# sm.net
KiCad netlist of a schematic drawn in Altium Designer
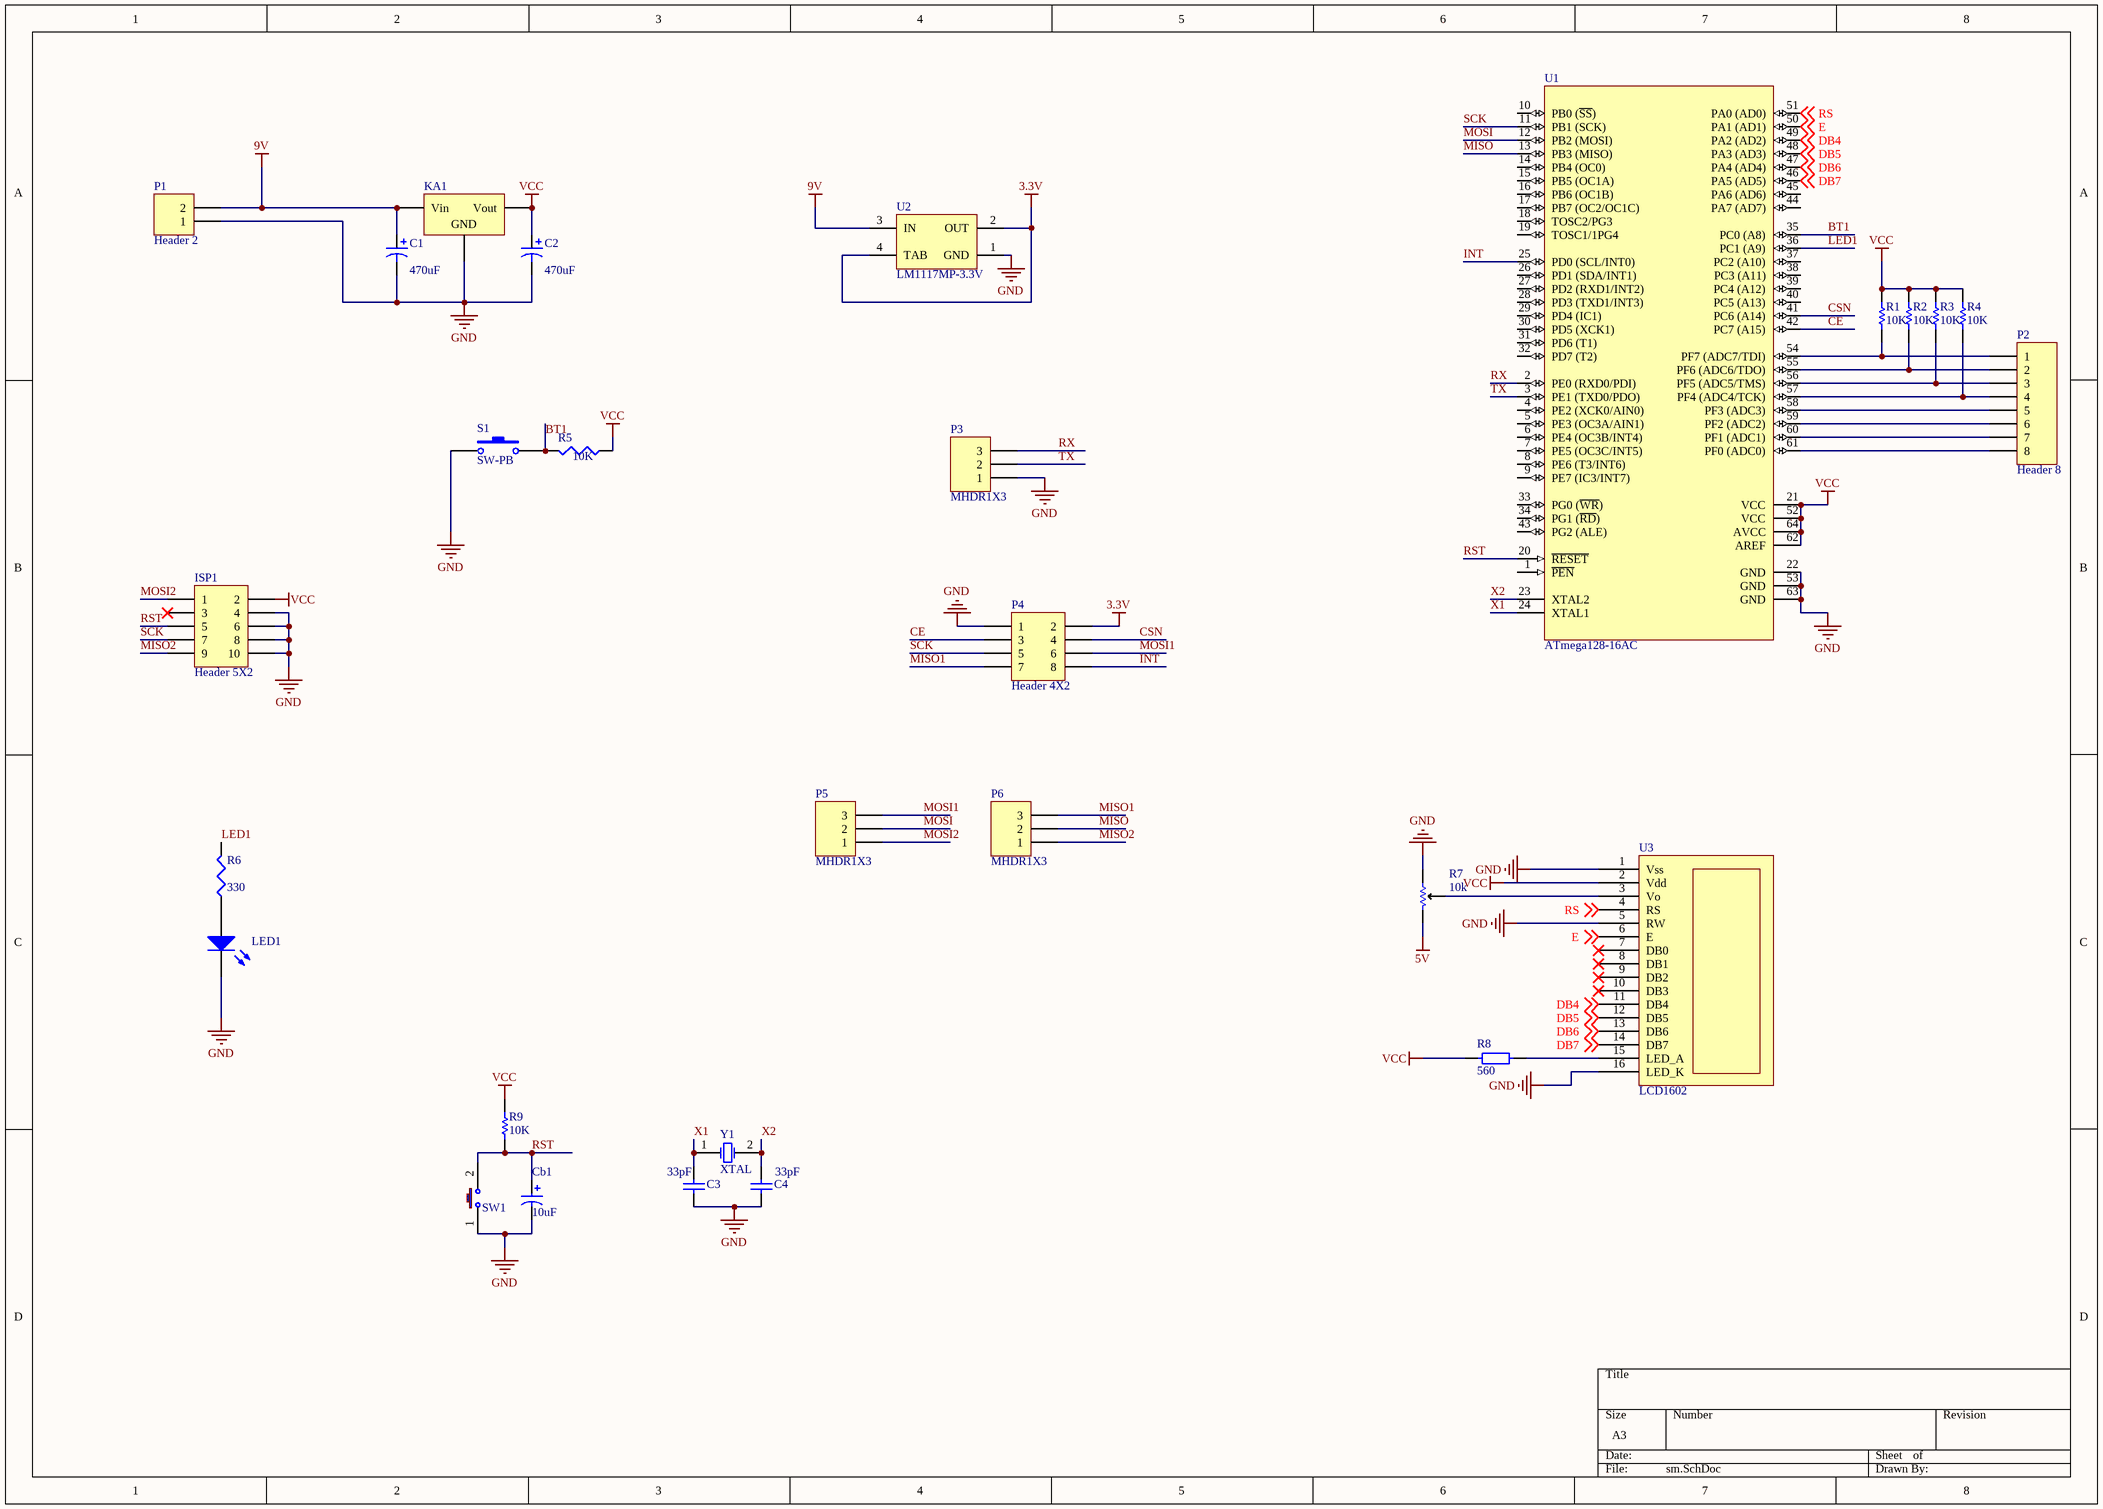
[diagram p0: sm.SchDoc]

(export (version "E")
  (design (tool "Eeschema 10.0.6"))
  (components
    (comp (ref "C1")
      (value "470uF")
      (footprint "CAPPR5-5x5")
      (description "Polarized Capacitor (Radial)")
      (fields (field (name "Comment") "Cap Pol1") (field (name "PUBLISHER") "Altium Limited"))
      (libsource (lib "Miscellaneous Devices") (part "Cap Pol1"))
    )
    (comp (ref "C2")
      (value "470uF")
      (footprint "CAPPR5-5x5")
      (description "Polarized Capacitor (Radial)")
      (fields (field (name "Comment") "Cap Pol1") (field (name "PUBLISHER") "Altium Limited"))
      (libsource (lib "Miscellaneous Devices") (part "Cap Pol1"))
    )
    (comp (ref "C3")
      (value "33pF")
      (footprint "SM/C_0805")
      (description "Capacitor")
      (fields (field (name "Comment") "Cap") (field (name "PUBLISHER") "Altium Limited"))
      (libsource (lib "Miscellaneous Devices") (part "Cap"))
    )
    (comp (ref "C4")
      (value "33pF")
      (footprint "SM/C_0805")
      (description "Capacitor")
      (fields (field (name "Comment") "Cap") (field (name "PUBLISHER") "Altium Limited"))
      (libsource (lib "Miscellaneous Devices") (part "Cap"))
    )
    (comp (ref "Cb1") (value "10uF") (footprint "SM/C_0805") (libsource (lib "DUYPRO2") (part "CAP POL 250")))
    (comp (ref "ISP1")
      (value "Header 5X2")
      (footprint "HDR2X5")
      (description "Header, 5-Pin, Dual row")
      (fields (field (name "PUBLISHER") "Altium Limited"))
      (libsource (lib "Miscellaneous Connectors") (part "Header 5X2"))
    )
    (comp (ref "KA1")
      (value "Volt Reg")
      (footprint "TO-220")
      (description "Voltage Regulator")
      (fields (field (name "PUBLISHER") "Altium Limited"))
      (libsource (lib "Miscellaneous Devices") (part "Volt Reg"))
    )
    (comp (ref "LED1")
      (value "LED3")
      (footprint "DSO-C2/D5.6")
      (description "Typical BLUE SiC LED")
      (fields (field (name "PUBLISHER") "Altium Limited"))
      (libsource (lib "Miscellaneous Devices") (part "LED3"))
    )
    (comp (ref "P1")
      (value "Header 2")
      (footprint "HDR1X2")
      (description "Header, 2-Pin")
      (fields (field (name "PUBLISHER") "Altium Limited"))
      (libsource (lib "Miscellaneous Connectors") (part "Header 2"))
    )
    (comp (ref "P2")
      (value "Header 8")
      (footprint "HDR1X8")
      (description "Header, 8-Pin")
      (fields (field (name "PUBLISHER") "Altium Limited"))
      (libsource (lib "Miscellaneous Connectors") (part "Header 8"))
    )
    (comp (ref "P3")
      (value "MHDR1X3")
      (footprint "MHDR1X3")
      (description "Header, 3-Pin")
      (fields (field (name "PUBLISHER") "Altium Limited"))
      (libsource (lib "Miscellaneous Connectors") (part "MHDR1X3"))
    )
    (comp (ref "P4")
      (value "Header 4X2")
      (footprint "HDR2X4")
      (description "Header, 4-Pin, Dual row")
      (fields (field (name "PUBLISHER") "Altium Limited"))
      (libsource (lib "Miscellaneous Connectors") (part "Header 4X2"))
    )
    (comp (ref "P5")
      (value "MHDR1X3")
      (footprint "MHDR1X3")
      (description "Header, 3-Pin")
      (fields (field (name "PUBLISHER") "Altium Limited"))
      (libsource (lib "Miscellaneous Connectors") (part "MHDR1X3"))
    )
    (comp (ref "P6")
      (value "MHDR1X3")
      (footprint "MHDR1X3")
      (description "Header, 3-Pin")
      (fields (field (name "PUBLISHER") "Altium Limited"))
      (libsource (lib "Miscellaneous Connectors") (part "MHDR1X3"))
    )
    (comp (ref "R1") (value "10K") (footprint "SM/C_0805") (libsource (lib "DUYPRO2") (part "R 300")))
    (comp (ref "R2") (value "10K") (footprint "SM/C_0805") (libsource (lib "DUYPRO2") (part "R 300")))
    (comp (ref "R3") (value "10K") (footprint "SM/C_0805") (libsource (lib "DUYPRO2") (part "R 300")))
    (comp (ref "R4") (value "10K") (footprint "SM/C_0805") (libsource (lib "DUYPRO2") (part "R 300")))
    (comp (ref "R5")
      (value "10K")
      (footprint "RESC1608L")
      (description "Resistor")
      (fields (field (name "Comment") "Res3") (field (name "PUBLISHER") "Altium Limited"))
      (libsource (lib "Miscellaneous Devices") (part "Res3"))
    )
    (comp (ref "R6")
      (value "330")
      (footprint "RESC1608L")
      (description "Resistor")
      (fields (field (name "Comment") "Res3") (field (name "PUBLISHER") "Altium Limited"))
      (libsource (lib "Miscellaneous Devices") (part "Res3"))
    )
    (comp (ref "R7") (value "10k") (footprint "BienTro") (libsource (lib "FUFO") (part "BienTro")))
    (comp (ref "R8") (value "560") (footprint "SM/C_0805") (libsource (lib "FUFO") (part "Resistor")))
    (comp (ref "R9") (value "10K") (footprint "SM/C_0805") (libsource (lib "DUYPRO2") (part "R 300")))
    (comp (ref "S1")
      (value "SW-PB")
      (footprint "SPST-2")
      (description "Switch")
      (fields (field (name "PUBLISHER") "Altium Limited"))
      (libsource (lib "Miscellaneous Devices") (part "SW-PB"))
    )
    (comp (ref "SW1")
      (value "BUTTON 2 PIN")
      (footprint "KEYSMALL2")
      (libsource (lib "DUYPRO2") (part "BUTTON 2 PIN"))
    )
    (comp (ref "U1")
      (value "ATmega128-16AC")
      (footprint "64A_N")
      (description "8-Bit AVR Microcontroller with 128K Bytes of In-System Programmable Flash Memory")
      (fields (field (name "PUBLISHER") "Altium Limited"))
      (libsource (lib "Atmel Microcontroller 8-Bit AVR") (part "ATmega128-16AC"))
    )
    (comp (ref "U2")
      (value "LM1117MP-3.3V")
      (footprint "SM/SOT223_1234")
      (description "800mA Low-Dropout Linear Regulator")
      (fields
        (field (name "PARTNUMBER") "LM1117MP-3.3")
        (field (name "MANUFACTURER") "National Semiconductor")
        (field (name "PUBLISHER") "Altium Limited")
      )
      (libsource (lib "NSC LDO") (part "LM1117MP-3.3"))
    )
    (comp (ref "U3") (value "LCD1602") (footprint "LCD1602") (libsource (lib "FUFO") (part "LCD1602")))
    (comp (ref "Y1")
      (value "XTAL")
      (footprint "CAPR5.08-7.8x3.2")
      (description "Crystal Oscillator")
      (fields (field (name "PUBLISHER") "Altium Limited"))
      (libsource (lib "Miscellaneous Devices") (part "XTAL"))
    )
  )
  (nets
    (net (code "1") (name "/BT1") (class "Default")
      (node (ref "R5") (pin "2") (pinfunction "2_2") (pintype "passive"))
      (node (ref "S1") (pin "2") (pinfunction "2_2") (pintype "passive"))
      (node (ref "U1") (pin "35") (pinfunction "PC0_(A8)_35") (pintype "bidirectional"))
    )
    (net (code "2") (name "/CE") (class "Default")
      (node (ref "P4") (pin "3") (pinfunction "3_3") (pintype "passive"))
      (node (ref "U1") (pin "42") (pinfunction "PC7_(A15)_42") (pintype "bidirectional"))
    )
    (net (code "3") (name "/CSN") (class "Default")
      (node (ref "P4") (pin "4") (pinfunction "4_4") (pintype "passive"))
      (node (ref "U1") (pin "41") (pinfunction "PC6_(A14)_41") (pintype "bidirectional"))
    )
    (net (code "4") (name "/INT") (class "Default")
      (node (ref "P4") (pin "8") (pinfunction "8_8") (pintype "passive"))
      (node (ref "U1") (pin "25") (pinfunction "PD0_(SCL/INT0)_25") (pintype "bidirectional"))
    )
    (net (code "5") (name "/LED1") (class "Default")
      (node (ref "R6") (pin "2") (pinfunction "2_2") (pintype "passive"))
      (node (ref "U1") (pin "36") (pinfunction "PC1_(A9)_36") (pintype "bidirectional"))
    )
    (net (code "6") (name "/MISO") (class "Default")
      (node (ref "P6") (pin "2") (pinfunction "2_2") (pintype "passive"))
      (node (ref "U1") (pin "13") (pinfunction "PB3_(MISO)_13") (pintype "bidirectional"))
    )
    (net (code "7") (name "/MISO1") (class "Default")
      (node (ref "P4") (pin "7") (pinfunction "7_7") (pintype "passive"))
      (node (ref "P6") (pin "3") (pinfunction "3_3") (pintype "passive"))
    )
    (net (code "8") (name "/MISO2") (class "Default")
      (node (ref "ISP1") (pin "9") (pinfunction "9_9") (pintype "passive"))
      (node (ref "P6") (pin "1") (pinfunction "1_1") (pintype "passive"))
    )
    (net (code "9") (name "/MOSI") (class "Default")
      (node (ref "P5") (pin "2") (pinfunction "2_2") (pintype "passive"))
      (node (ref "U1") (pin "12") (pinfunction "PB2_(MOSI)_12") (pintype "bidirectional"))
    )
    (net (code "10") (name "/MOSI1") (class "Default")
      (node (ref "P4") (pin "6") (pinfunction "6_6") (pintype "passive"))
      (node (ref "P5") (pin "3") (pinfunction "3_3") (pintype "passive"))
    )
    (net (code "11") (name "/MOSI2") (class "Default")
      (node (ref "ISP1") (pin "1") (pinfunction "1_1") (pintype "passive"))
      (node (ref "P5") (pin "1") (pinfunction "1_1") (pintype "passive"))
    )
    (net (code "12") (name "/RST") (class "Default")
      (node (ref "Cb1") (pin "1") (pinfunction "1_1") (pintype "passive"))
      (node (ref "ISP1") (pin "5") (pinfunction "5_5") (pintype "passive"))
      (node (ref "R9") (pin "1") (pinfunction "1_1") (pintype "passive"))
      (node (ref "SW1") (pin "2") (pinfunction "2_2") (pintype "passive"))
      (node (ref "U1") (pin "20") (pinfunction "~{RESET}_20") (pintype "input"))
    )
    (net (code "13") (name "/RX") (class "Default")
      (node (ref "P3") (pin "3") (pinfunction "3_3") (pintype "passive"))
      (node (ref "U1") (pin "2") (pinfunction "PE0_(RXD0/PDI)_2") (pintype "bidirectional"))
    )
    (net (code "14") (name "/SCK") (class "Default")
      (node (ref "ISP1") (pin "7") (pinfunction "7_7") (pintype "passive"))
      (node (ref "P4") (pin "5") (pinfunction "5_5") (pintype "passive"))
      (node (ref "U1") (pin "11") (pinfunction "PB1_(SCK)_11") (pintype "bidirectional"))
    )
    (net (code "15") (name "/TX") (class "Default")
      (node (ref "P3") (pin "2") (pinfunction "2_2") (pintype "passive"))
      (node (ref "U1") (pin "3") (pinfunction "PE1_(TXD0/PDO)_3") (pintype "bidirectional"))
    )
    (net (code "16") (name "/X1") (class "Default")
      (node (ref "C3") (pin "2") (pinfunction "2_2") (pintype "passive"))
      (node (ref "U1") (pin "24") (pinfunction "XTAL1_24") (pintype "passive"))
      (node (ref "Y1") (pin "1") (pinfunction "OSC1_1") (pintype "passive"))
    )
    (net (code "17") (name "/X2") (class "Default")
      (node (ref "C4") (pin "2") (pinfunction "2_2") (pintype "passive"))
      (node (ref "U1") (pin "23") (pinfunction "XTAL2_23") (pintype "passive"))
      (node (ref "Y1") (pin "2") (pinfunction "OSC2_2") (pintype "passive"))
    )
    (net (code "18") (name "3.3V") (class "Default")
      (node (ref "P4") (pin "2") (pinfunction "2_2") (pintype "passive"))
      (node (ref "U2") (pin "2") (pinfunction "OUT_2") (pintype "power_in"))
      (node (ref "U2") (pin "4") (pinfunction "TAB_4") (pintype "power_in"))
    )
    (net (code "19") (name "5V") (class "Default")
      (node (ref "R7") (pin "2") (pinfunction "2_2") (pintype "passive"))
    )
    (net (code "20") (name "9V") (class "Default")
      (node (ref "C1") (pin "1") (pinfunction "1_1") (pintype "passive"))
      (node (ref "KA1") (pin "1") (pinfunction "Vin_1") (pintype "passive"))
      (node (ref "P1") (pin "2") (pinfunction "2_2") (pintype "passive"))
      (node (ref "U2") (pin "3") (pinfunction "IN_3") (pintype "power_in"))
    )
    (net (code "21") (name "DB4") (class "Default")
      (node (ref "U1") (pin "49") (pinfunction "PA2_(AD2)_49") (pintype "bidirectional"))
      (node (ref "U3") (pin "11") (pinfunction "DB4_11") (pintype "passive"))
    )
    (net (code "22") (name "DB5") (class "Default")
      (node (ref "U1") (pin "48") (pinfunction "PA3_(AD3)_48") (pintype "bidirectional"))
      (node (ref "U3") (pin "12") (pinfunction "DB5_12") (pintype "passive"))
    )
    (net (code "23") (name "DB6") (class "Default")
      (node (ref "U1") (pin "47") (pinfunction "PA4_(AD4)_47") (pintype "bidirectional"))
      (node (ref "U3") (pin "13") (pinfunction "DB6_13") (pintype "passive"))
    )
    (net (code "24") (name "DB7") (class "Default")
      (node (ref "U1") (pin "46") (pinfunction "PA5_(AD5)_46") (pintype "bidirectional"))
      (node (ref "U3") (pin "14") (pinfunction "DB7_14") (pintype "passive"))
    )
    (net (code "25") (name "E") (class "Default")
      (node (ref "U1") (pin "50") (pinfunction "PA1_(AD1)_50") (pintype "bidirectional"))
      (node (ref "U3") (pin "6") (pinfunction "E_6") (pintype "passive"))
    )
    (net (code "26") (name "GND") (class "Default")
      (node (ref "C1") (pin "2") (pinfunction "2_2") (pintype "passive"))
      (node (ref "C2") (pin "2") (pinfunction "2_2") (pintype "passive"))
      (node (ref "C3") (pin "1") (pinfunction "1_1") (pintype "passive"))
      (node (ref "C4") (pin "1") (pinfunction "1_1") (pintype "passive"))
      (node (ref "Cb1") (pin "2") (pinfunction "2_2") (pintype "passive"))
      (node (ref "ISP1") (pin "10") (pinfunction "10_10") (pintype "passive"))
      (node (ref "ISP1") (pin "4") (pinfunction "4_4") (pintype "passive"))
      (node (ref "ISP1") (pin "6") (pinfunction "6_6") (pintype "passive"))
      (node (ref "ISP1") (pin "8") (pinfunction "8_8") (pintype "passive"))
      (node (ref "KA1") (pin "2") (pinfunction "GND_2") (pintype "passive"))
      (node (ref "LED1") (pin "2") (pinfunction "K_2") (pintype "passive"))
      (node (ref "P1") (pin "1") (pinfunction "1_1") (pintype "passive"))
      (node (ref "P3") (pin "1") (pinfunction "1_1") (pintype "passive"))
      (node (ref "P4") (pin "1") (pinfunction "1_1") (pintype "passive"))
      (node (ref "R7") (pin "0") (pinfunction "0_0") (pintype "passive"))
      (node (ref "S1") (pin "1") (pinfunction "1_1") (pintype "passive"))
      (node (ref "SW1") (pin "1") (pinfunction "1_1") (pintype "passive"))
      (node (ref "U1") (pin "22") (pinfunction "GND_22") (pintype "power_in"))
      (node (ref "U1") (pin "53") (pinfunction "GND_53") (pintype "power_in"))
      (node (ref "U1") (pin "63") (pinfunction "GND_63") (pintype "power_in"))
      (node (ref "U2") (pin "1") (pinfunction "GND_1") (pintype "power_in"))
      (node (ref "U3") (pin "1") (pinfunction "Vss_1") (pintype "passive"))
      (node (ref "U3") (pin "16") (pinfunction "LED_K_16") (pintype "passive"))
      (node (ref "U3") (pin "5") (pinfunction "RW_5") (pintype "passive"))
    )
    (net (code "27") (name "Net-(LED1-A)") (class "Default")
      (node (ref "LED1") (pin "1") (pinfunction "A_1") (pintype "passive"))
      (node (ref "R6") (pin "1") (pinfunction "1_1") (pintype "passive"))
    )
    (net (code "28") (name "Net-(U1-PF0_(ADC0))") (class "Default")
      (node (ref "P2") (pin "8") (pinfunction "8_8") (pintype "passive"))
      (node (ref "U1") (pin "61") (pinfunction "PF0_(ADC0)_61") (pintype "bidirectional"))
    )
    (net (code "29") (name "Net-(U1-PF1_(ADC1))") (class "Default")
      (node (ref "P2") (pin "7") (pinfunction "7_7") (pintype "passive"))
      (node (ref "U1") (pin "60") (pinfunction "PF1_(ADC1)_60") (pintype "bidirectional"))
    )
    (net (code "30") (name "Net-(U1-PF2_(ADC2))") (class "Default")
      (node (ref "P2") (pin "6") (pinfunction "6_6") (pintype "passive"))
      (node (ref "U1") (pin "59") (pinfunction "PF2_(ADC2)_59") (pintype "bidirectional"))
    )
    (net (code "31") (name "Net-(U1-PF3_(ADC3))") (class "Default")
      (node (ref "P2") (pin "5") (pinfunction "5_5") (pintype "passive"))
      (node (ref "U1") (pin "58") (pinfunction "PF3_(ADC3)_58") (pintype "bidirectional"))
    )
    (net (code "32") (name "Net-(U1-PF4_(ADC4{slash}TCK))") (class "Default")
      (node (ref "P2") (pin "4") (pinfunction "4_4") (pintype "passive"))
      (node (ref "R4") (pin "1") (pinfunction "1_1") (pintype "passive"))
      (node (ref "U1") (pin "57") (pinfunction "PF4_(ADC4/TCK)_57") (pintype "bidirectional"))
    )
    (net (code "33") (name "Net-(U1-PF5_(ADC5{slash}TMS))") (class "Default")
      (node (ref "P2") (pin "3") (pinfunction "3_3") (pintype "passive"))
      (node (ref "R3") (pin "1") (pinfunction "1_1") (pintype "passive"))
      (node (ref "U1") (pin "56") (pinfunction "PF5_(ADC5/TMS)_56") (pintype "bidirectional"))
    )
    (net (code "34") (name "Net-(U1-PF6_(ADC6{slash}TDO))") (class "Default")
      (node (ref "P2") (pin "2") (pinfunction "2_2") (pintype "passive"))
      (node (ref "R2") (pin "1") (pinfunction "1_1") (pintype "passive"))
      (node (ref "U1") (pin "55") (pinfunction "PF6_(ADC6/TDO)_55") (pintype "bidirectional"))
    )
    (net (code "35") (name "Net-(U1-PF7_(ADC7{slash}TDI))") (class "Default")
      (node (ref "P2") (pin "1") (pinfunction "1_1") (pintype "passive"))
      (node (ref "R1") (pin "1") (pinfunction "1_1") (pintype "passive"))
      (node (ref "U1") (pin "54") (pinfunction "PF7_(ADC7/TDI)_54") (pintype "bidirectional"))
    )
    (net (code "36") (name "Net-(U3-LED_A)") (class "Default")
      (node (ref "R8") (pin "2") (pinfunction "2_2") (pintype "passive"))
      (node (ref "U3") (pin "15") (pinfunction "LED_A_15") (pintype "passive"))
    )
    (net (code "37") (name "Net-(U3-Vo)") (class "Default")
      (node (ref "R7") (pin "1") (pinfunction "1_1") (pintype "passive"))
      (node (ref "U3") (pin "3") (pinfunction "Vo_3") (pintype "passive"))
    )
    (net (code "38") (name "RS") (class "Default")
      (node (ref "U1") (pin "51") (pinfunction "PA0_(AD0)_51") (pintype "bidirectional"))
      (node (ref "U3") (pin "4") (pinfunction "RS_4") (pintype "passive"))
    )
    (net (code "39") (name "VCC") (class "Default")
      (node (ref "C2") (pin "1") (pinfunction "1_1") (pintype "passive"))
      (node (ref "ISP1") (pin "2") (pinfunction "2_2") (pintype "passive"))
      (node (ref "KA1") (pin "3") (pinfunction "Vout_3") (pintype "passive"))
      (node (ref "R1") (pin "2") (pinfunction "2_2") (pintype "passive"))
      (node (ref "R2") (pin "2") (pinfunction "2_2") (pintype "passive"))
      (node (ref "R3") (pin "2") (pinfunction "2_2") (pintype "passive"))
      (node (ref "R4") (pin "2") (pinfunction "2_2") (pintype "passive"))
      (node (ref "R5") (pin "1") (pinfunction "1_1") (pintype "passive"))
      (node (ref "R8") (pin "1") (pinfunction "1_1") (pintype "passive"))
      (node (ref "R9") (pin "2") (pinfunction "2_2") (pintype "passive"))
      (node (ref "U1") (pin "21") (pinfunction "VCC_21") (pintype "power_in"))
      (node (ref "U1") (pin "52") (pinfunction "VCC_52") (pintype "power_in"))
      (node (ref "U1") (pin "62") (pinfunction "AREF_62") (pintype "passive"))
      (node (ref "U1") (pin "64") (pinfunction "AVCC_64") (pintype "power_in"))
      (node (ref "U3") (pin "2") (pinfunction "Vdd_2") (pintype "passive"))
    )
    (net (code "40") (name "unconnected-(ISP1-Pad3)") (class "Default")
      (node (ref "ISP1") (pin "3") (pinfunction "3_3") (pintype "passive+no_connect"))
    )
    (net (code "41") (name "unconnected-(U1-PA6_(AD6)-Pad45)") (class "Default")
      (node (ref "U1") (pin "45") (pinfunction "PA6_(AD6)_45") (pintype "bidirectional"))
    )
    (net (code "42") (name "unconnected-(U1-PA7_(AD7)-Pad44)") (class "Default")
      (node (ref "U1") (pin "44") (pinfunction "PA7_(AD7)_44") (pintype "bidirectional"))
    )
    (net (code "43") (name "unconnected-(U1-PB0_(~{SS})-Pad10)") (class "Default")
      (node (ref "U1") (pin "10") (pinfunction "PB0_(~{SS})_10") (pintype "bidirectional"))
    )
    (net (code "44") (name "unconnected-(U1-PB4_(OC0)-Pad14)") (class "Default")
      (node (ref "U1") (pin "14") (pinfunction "PB4_(OC0)_14") (pintype "bidirectional"))
    )
    (net (code "45") (name "unconnected-(U1-PB5_(OC1A)-Pad15)") (class "Default")
      (node (ref "U1") (pin "15") (pinfunction "PB5_(OC1A)_15") (pintype "bidirectional"))
    )
    (net (code "46") (name "unconnected-(U1-PB6_(OC1B)-Pad16)") (class "Default")
      (node (ref "U1") (pin "16") (pinfunction "PB6_(OC1B)_16") (pintype "bidirectional"))
    )
    (net (code "47") (name "unconnected-(U1-PB7_(OC2{slash}OC1C)-Pad17)") (class "Default")
      (node (ref "U1") (pin "17") (pinfunction "PB7_(OC2/OC1C)_17") (pintype "bidirectional"))
    )
    (net (code "48") (name "unconnected-(U1-PC2_(A10)-Pad37)") (class "Default")
      (node (ref "U1") (pin "37") (pinfunction "PC2_(A10)_37") (pintype "bidirectional"))
    )
    (net (code "49") (name "unconnected-(U1-PC3_(A11)-Pad38)") (class "Default")
      (node (ref "U1") (pin "38") (pinfunction "PC3_(A11)_38") (pintype "bidirectional"))
    )
    (net (code "50") (name "unconnected-(U1-PC4_(A12)-Pad39)") (class "Default")
      (node (ref "U1") (pin "39") (pinfunction "PC4_(A12)_39") (pintype "bidirectional"))
    )
    (net (code "51") (name "unconnected-(U1-PC5_(A13)-Pad40)") (class "Default")
      (node (ref "U1") (pin "40") (pinfunction "PC5_(A13)_40") (pintype "bidirectional"))
    )
    (net (code "52") (name "unconnected-(U1-PD1_(SDA{slash}INT1)-Pad26)") (class "Default")
      (node (ref "U1") (pin "26") (pinfunction "PD1_(SDA/INT1)_26") (pintype "bidirectional"))
    )
    (net (code "53") (name "unconnected-(U1-PD2_(RXD1{slash}INT2)-Pad27)") (class "Default")
      (node (ref "U1") (pin "27") (pinfunction "PD2_(RXD1/INT2)_27") (pintype "bidirectional"))
    )
    (net (code "54") (name "unconnected-(U1-PD3_(TXD1{slash}INT3)-Pad28)") (class "Default")
      (node (ref "U1") (pin "28") (pinfunction "PD3_(TXD1/INT3)_28") (pintype "bidirectional"))
    )
    (net (code "55") (name "unconnected-(U1-PD4_(IC1)-Pad29)") (class "Default")
      (node (ref "U1") (pin "29") (pinfunction "PD4_(IC1)_29") (pintype "bidirectional"))
    )
    (net (code "56") (name "unconnected-(U1-PD5_(XCK1)-Pad30)") (class "Default")
      (node (ref "U1") (pin "30") (pinfunction "PD5_(XCK1)_30") (pintype "bidirectional"))
    )
    (net (code "57") (name "unconnected-(U1-PD6_(T1)-Pad31)") (class "Default")
      (node (ref "U1") (pin "31") (pinfunction "PD6_(T1)_31") (pintype "bidirectional"))
    )
    (net (code "58") (name "unconnected-(U1-PD7_(T2)-Pad32)") (class "Default")
      (node (ref "U1") (pin "32") (pinfunction "PD7_(T2)_32") (pintype "bidirectional"))
    )
    (net (code "59") (name "unconnected-(U1-PE2_(XCK0{slash}AIN0)-Pad4)") (class "Default")
      (node (ref "U1") (pin "4") (pinfunction "PE2_(XCK0/AIN0)_4") (pintype "bidirectional"))
    )
    (net (code "60") (name "unconnected-(U1-PE3_(OC3A{slash}AIN1)-Pad5)") (class "Default")
      (node (ref "U1") (pin "5") (pinfunction "PE3_(OC3A/AIN1)_5") (pintype "bidirectional"))
    )
    (net (code "61") (name "unconnected-(U1-PE4_(OC3B{slash}INT4)-Pad6)") (class "Default")
      (node (ref "U1") (pin "6") (pinfunction "PE4_(OC3B/INT4)_6") (pintype "bidirectional"))
    )
    (net (code "62") (name "unconnected-(U1-PE5_(OC3C{slash}INT5)-Pad7)") (class "Default")
      (node (ref "U1") (pin "7") (pinfunction "PE5_(OC3C/INT5)_7") (pintype "bidirectional"))
    )
    (net (code "63") (name "unconnected-(U1-PE6_(T3{slash}INT6)-Pad8)") (class "Default")
      (node (ref "U1") (pin "8") (pinfunction "PE6_(T3/INT6)_8") (pintype "bidirectional"))
    )
    (net (code "64") (name "unconnected-(U1-PE7_(IC3{slash}INT7)-Pad9)") (class "Default")
      (node (ref "U1") (pin "9") (pinfunction "PE7_(IC3/INT7)_9") (pintype "bidirectional"))
    )
    (net (code "65") (name "unconnected-(U1-PG0_(~{WR})-Pad33)") (class "Default")
      (node (ref "U1") (pin "33") (pinfunction "PG0_(~{WR})_33") (pintype "bidirectional"))
    )
    (net (code "66") (name "unconnected-(U1-PG1_(~{RD})-Pad34)") (class "Default")
      (node (ref "U1") (pin "34") (pinfunction "PG1_(~{RD})_34") (pintype "bidirectional"))
    )
    (net (code "67") (name "unconnected-(U1-PG2_(ALE)-Pad43)") (class "Default")
      (node (ref "U1") (pin "43") (pinfunction "PG2_(ALE)_43") (pintype "bidirectional"))
    )
    (net (code "68") (name "unconnected-(U1-TOSC1{slash}1PG4-Pad19)") (class "Default")
      (node (ref "U1") (pin "19") (pinfunction "TOSC1/1PG4_19") (pintype "bidirectional"))
    )
    (net (code "69") (name "unconnected-(U1-TOSC2{slash}PG3-Pad18)") (class "Default")
      (node (ref "U1") (pin "18") (pinfunction "TOSC2/PG3_18") (pintype "bidirectional"))
    )
    (net (code "70") (name "unconnected-(U1-~{PEN}-Pad1)") (class "Default")
      (node (ref "U1") (pin "1") (pinfunction "~{PEN}_1") (pintype "input"))
    )
    (net (code "71") (name "unconnected-(U3-DB0-Pad7)") (class "Default")
      (node (ref "U3") (pin "7") (pinfunction "DB0_7") (pintype "passive+no_connect"))
    )
    (net (code "72") (name "unconnected-(U3-DB1-Pad8)") (class "Default")
      (node (ref "U3") (pin "8") (pinfunction "DB1_8") (pintype "passive+no_connect"))
    )
    (net (code "73") (name "unconnected-(U3-DB2-Pad9)") (class "Default")
      (node (ref "U3") (pin "9") (pinfunction "DB2_9") (pintype "passive+no_connect"))
    )
    (net (code "74") (name "unconnected-(U3-DB3-Pad10)") (class "Default")
      (node (ref "U3") (pin "10") (pinfunction "DB3_10") (pintype "passive+no_connect"))
    )
  )
)
